# design.net
KiCad netlist of a schematic drawn in EasyEDA Pro
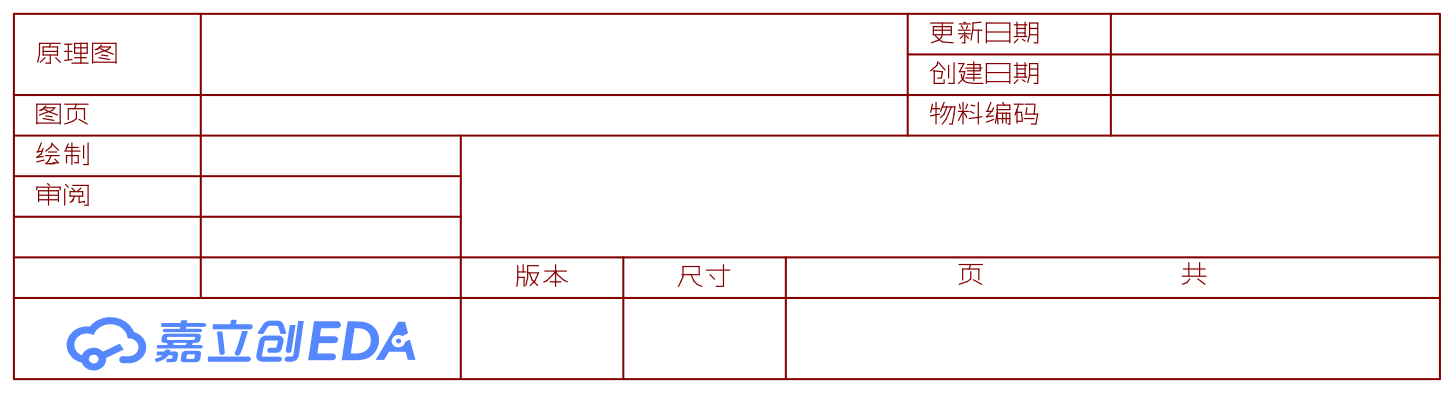
[diagram p0: 主控MCU]
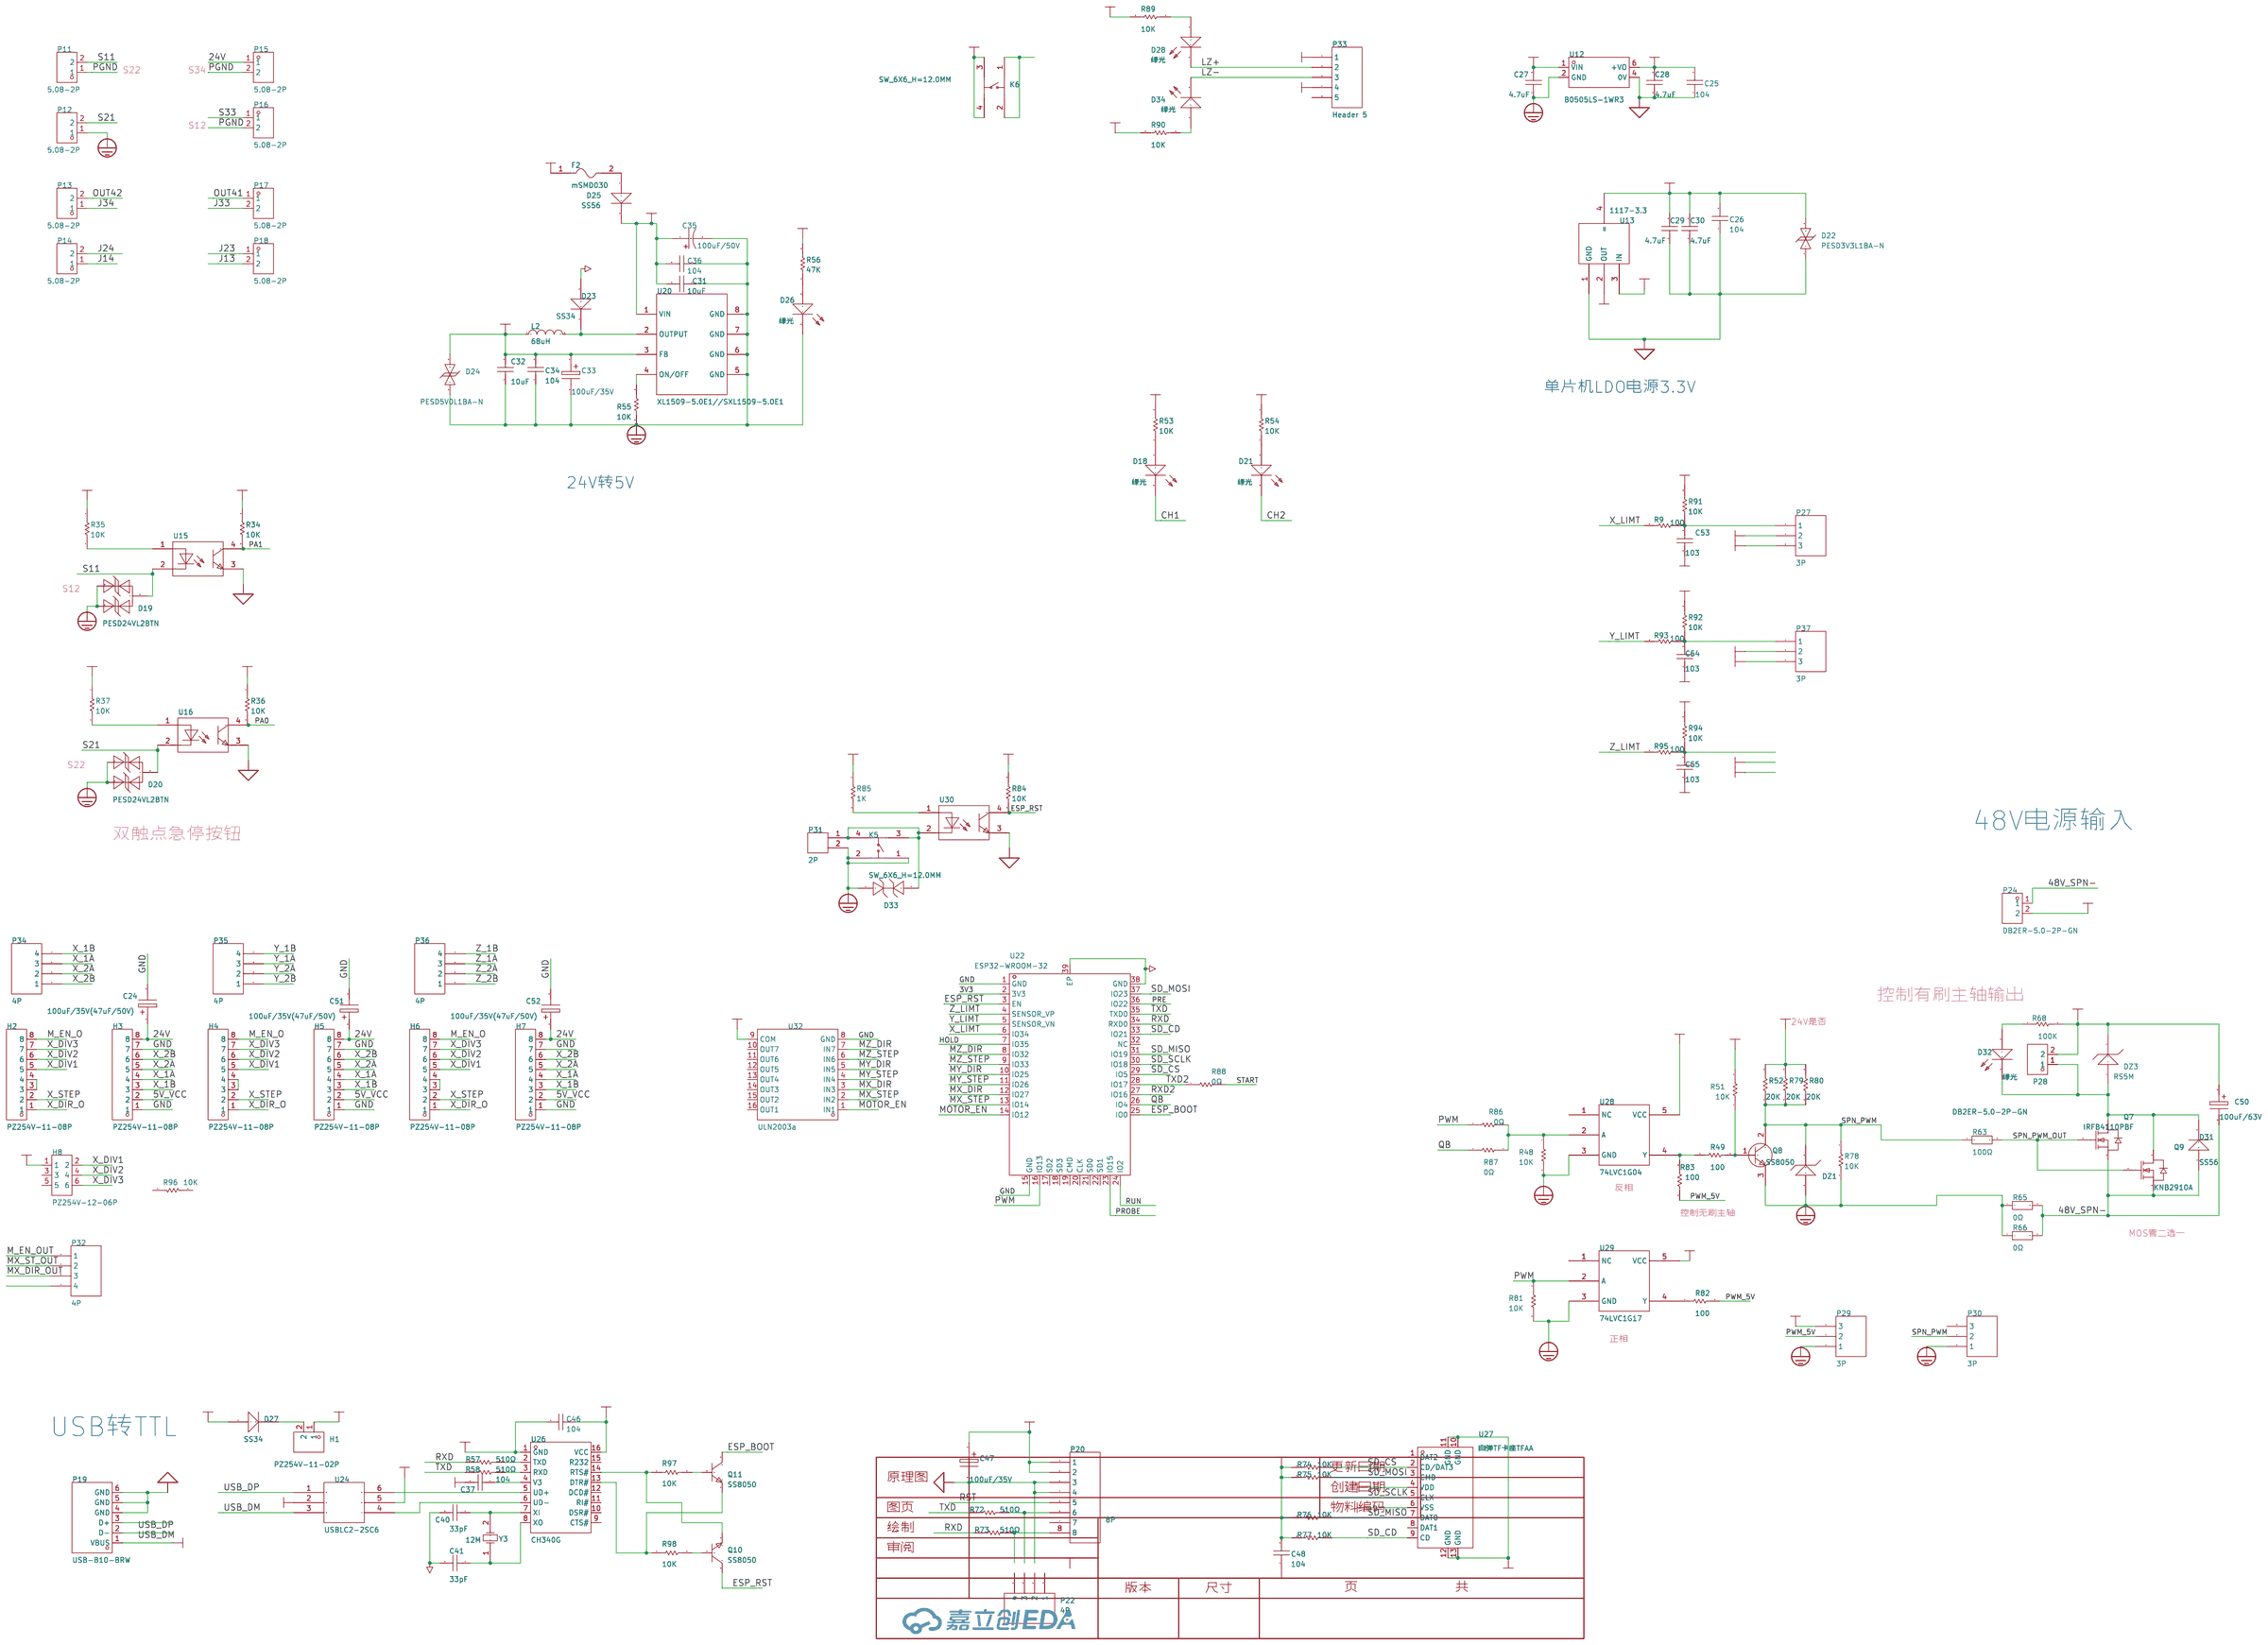
[diagram p1: 电源]

(export (version "E")
  (design (tool "Eeschema 10.0.6"))
  (components
    (comp (ref "C24")
      (value "100uF/35V(47uF/50V)")
      (footprint "easyedapro:电解电容贴片10x10")
      (libsource (lib "easyedapro") (part "ELECTRO1"))
    )
    (comp (ref "C25") (value "104") (libsource (lib "easyedapro") (part "CAP")))
    (comp (ref "C26")
      (value "104")
      (footprint "easyedapro:0603C")
      (description "Capacitor (Semiconductor SIM Model)")
      (libsource (lib "easyedapro") (part "Cap Semi"))
    )
    (comp (ref "C27") (value "4.7uF") (libsource (lib "easyedapro") (part "CAP")))
    (comp (ref "C28") (value "4.7uF") (libsource (lib "easyedapro") (part "CAP")))
    (comp (ref "C29") (value "4.7uF") (libsource (lib "easyedapro") (part "CAP")))
    (comp (ref "C30") (value "4.7uF") (libsource (lib "easyedapro") (part "CAP")))
    (comp (ref "C31") (value "10uF") (libsource (lib "easyedapro") (part "CAP")))
    (comp (ref "C32") (value "10uF") (libsource (lib "easyedapro") (part "CAP")))
    (comp (ref "C33")
      (value "100uF/35V")
      (footprint "easyedapro:0603C")
      (libsource (lib "easyedapro") (part "ELECTRO1"))
    )
    (comp (ref "C34")
      (value "104")
      (footprint "easyedapro:0603C")
      (description "Capacitor (Semiconductor SIM Model)")
      (libsource (lib "easyedapro") (part "Cap Semi"))
    )
    (comp (ref "C35")
      (value "100uF/50V")
      (footprint "easyedapro:CAP-SMD_BD10.0-L10.3-W10.3-LS11.0-R-RD")
      (fields (field (name "Manufacturer Part") "VZH101M1HTR-1008") (field (name "Manufacturer") "lelon(立隆)"))
      (libsource (lib "easyedapro") (part "VZH101M1HTR-1008"))
    )
    (comp (ref "C36")
      (value "104")
      (footprint "easyedapro:0603C")
      (description "Capacitor (Semiconductor SIM Model)")
      (libsource (lib "easyedapro") (part "Cap Semi"))
    )
    (comp (ref "C37")
      (value "104")
      (footprint "easyedapro:0603C")
      (description "Capacitor (Semiconductor SIM Model)")
      (libsource (lib "easyedapro") (part "Cap Semi"))
    )
    (comp (ref "C40")
      (value "18pF")
      (footprint "easyedapro:0603C")
      (description "Capacitor (Semiconductor SIM Model)")
      (libsource (lib "easyedapro") (part "Cap Semi"))
    )
    (comp (ref "C41")
      (value "18pF")
      (footprint "easyedapro:0603C")
      (description "Capacitor (Semiconductor SIM Model)")
      (libsource (lib "easyedapro") (part "Cap Semi"))
    )
    (comp (ref "C46")
      (value "104")
      (footprint "easyedapro:0603C")
      (description "Capacitor (Semiconductor SIM Model)")
      (libsource (lib "easyedapro") (part "Cap Semi"))
    )
    (comp (ref "C47")
      (value "100uF/35V")
      (footprint "easyedapro:电解电容贴片10x10")
      (libsource (lib "easyedapro") (part "ELECTRO1"))
    )
    (comp (ref "C48")
      (value "104")
      (footprint "easyedapro:11")
      (description "Capacitor (Semiconductor SIM Model)")
      (libsource (lib "easyedapro") (part "Cap Semi"))
    )
    (comp (ref "C50")
      (value "100uF/63V")
      (footprint "easyedapro:电解电容贴片10x10")
      (libsource (lib "easyedapro") (part "ELECTRO1"))
    )
    (comp (ref "C51")
      (value "100uF/35V(47uF/50V)")
      (footprint "easyedapro:电解电容贴片10x10")
      (libsource (lib "easyedapro") (part "ELECTRO1"))
    )
    (comp (ref "C52")
      (value "100uF/35V(47uF/50V)")
      (footprint "easyedapro:电解电容贴片10x10")
      (libsource (lib "easyedapro") (part "ELECTRO1"))
    )
    (comp (ref "C53") (value "103") (footprint "easyedapro:11") (libsource (lib "") (part "CAP_1")))
    (comp (ref "C54") (value "103") (footprint "easyedapro:11") (libsource (lib "") (part "CAP_1")))
    (comp (ref "C55") (value "103") (footprint "easyedapro:11") (libsource (lib "") (part "CAP_1")))
    (comp (ref "D18")
      (value "绿光")
      (footprint "easyedapro:0603LED")
      (libsource (lib "easyedapro") (part "LED"))
    )
    (comp (ref "D19")
      (value "PESD24VL2BTN")
      (footprint "easyedapro:SOT-23-3_L2.9-W1.6-P1.90-LS2.8-BR")
      (description "极性:Bidirectional;反向关断电压（典型值）:24V (Max);击穿电压（最小值）:26.7V;箝位电压:48V;峰值脉冲电流（10/1000us）:6A (8/20us);")
      (fields (field (name "Manufacturer") "BORN伯恩半导体"))
      (libsource (lib "easyedapro") (part "PESD24VL2BTN"))
    )
    (comp (ref "D20")
      (value "PESD24VL2BTN")
      (footprint "easyedapro:SOT-23-3_L2.9-W1.6-P1.90-LS2.8-BR")
      (description "极性:Bidirectional;反向关断电压（典型值）:24V (Max);击穿电压（最小值）:26.7V;箝位电压:48V;峰值脉冲电流（10/1000us）:6A (8/20us);")
      (fields (field (name "Manufacturer") "BORN伯恩半导体"))
      (libsource (lib "easyedapro") (part "PESD24VL2BTN"))
    )
    (comp (ref "D21")
      (value "绿光")
      (footprint "easyedapro:0603LED")
      (libsource (lib "easyedapro") (part "LED"))
    )
    (comp (ref "D22")
      (value "PESD3V3L1BA-N")
      (footprint "easyedapro:SOD-523_L1.2-W0.8-LS1.6-BI")
      (description "极性:Bidirectional;反向关断电压（典型值）:5V (Max);击穿电压（最小值）:6V;箝位电压:15V;峰值脉冲电流（10/1000us）:5A (8/20us);")
      (fields (field (name "Manufacturer") "BORN伯恩半导体"))
      (libsource (lib "easyedapro") (part "PESD5V0S1BBN"))
    )
    (comp (ref "D23") (value "SS34") (libsource (lib "easyedapro") (part "1N4148")))
    (comp (ref "D24")
      (value "PESD5V0L1BA-N")
      (footprint "easyedapro:SOD-523_L1.2-W0.8-LS1.6-BI")
      (description "极性:Bidirectional;反向关断电压（典型值）:5V (Max);击穿电压（最小值）:6V;箝位电压:15V;峰值脉冲电流（10/1000us）:5A (8/20us);")
      (fields (field (name "Manufacturer") "BORN伯恩半导体"))
      (libsource (lib "easyedapro") (part "PESD5V0S1BBN"))
    )
    (comp (ref "D25") (value "SS56") (footprint "easyedapro:SMA") (libsource (lib "") (part "1N4148_1")))
    (comp (ref "D26")
      (value "绿光")
      (footprint "easyedapro:0603LED")
      (libsource (lib "easyedapro") (part "LED"))
    )
    (comp (ref "D27") (value "SS34") (footprint "easyedapro:SMA") (libsource (lib "") (part "1N4148_1")))
    (comp (ref "D28")
      (value "绿光")
      (footprint "easyedapro:0603LED")
      (libsource (lib "easyedapro") (part "LED"))
    )
    (comp (ref "D31") (value "SS56") (libsource (lib "easyedapro") (part "1N4148")))
    (comp (ref "D32")
      (value "绿光")
      (footprint "easyedapro:0603LED")
      (libsource (lib "easyedapro") (part "LED"))
    )
    (comp (ref "D33")
      (value "ESD05V52D-C")
      (footprint "easyedapro:SOD-523_L1.2-W0.8-LS1.6-BI")
      (fields (field (name "Manufacturer") "TWGMC(台湾迪嘉)"))
      (libsource (lib "easyedapro") (part "ESD05V52D-C"))
    )
    (comp (ref "D34")
      (value "绿光")
      (footprint "easyedapro:0603LED")
      (libsource (lib "easyedapro") (part "LED"))
    )
    (comp (ref "DZ1") (value "--ѹ------SMAZ10V") (libsource (lib "easyedapro") (part "ѹ")))
    (comp (ref "DZ3") (value "RS5M") (libsource (lib "easyedapro") (part "ѹ")))
    (comp (ref "F2")
      (value "mSMD030")
      (footprint "easyedapro:F1812")
      (description "最大电压:30V;最大电流:100A;保持电流:300mA;跳闸电流:600mA;")
      (fields (field (name "Manufacturer") "台湾陆海"))
      (libsource (lib "easyedapro") (part "mSMD030"))
    )
    (comp (ref "H1")
      (value "PZ254V-11-02P")
      (footprint "easyedapro:HDR-TH_2P-P2.54-V-M")
      (fields (field (name "Manufacturer") "XFCN(兴飞)"))
      (libsource (lib "easyedapro") (part "PZ254V-11-02P"))
    )
    (comp (ref "H2")
      (value "PZ254V-11-08P")
      (footprint "easyedapro:HDR-TH_8P-P2.54-V-M")
      (fields (field (name "Manufacturer") "XFCN(兴飞)"))
      (libsource (lib "easyedapro") (part "PZ254V-11-08P"))
    )
    (comp (ref "H3")
      (value "PZ254V-11-08P")
      (footprint "easyedapro:HDR-TH_8P-P2.54-V-M")
      (fields (field (name "Manufacturer") "XFCN(兴飞)"))
      (libsource (lib "easyedapro") (part "PZ254V-11-08P"))
    )
    (comp (ref "H4")
      (value "PZ254V-11-08P")
      (footprint "easyedapro:HDR-TH_8P-P2.54-V-M")
      (fields (field (name "Manufacturer") "XFCN(兴飞)"))
      (libsource (lib "easyedapro") (part "PZ254V-11-08P"))
    )
    (comp (ref "H5")
      (value "PZ254V-11-08P")
      (footprint "easyedapro:HDR-TH_8P-P2.54-V-M")
      (fields (field (name "Manufacturer") "XFCN(兴飞)"))
      (libsource (lib "easyedapro") (part "PZ254V-11-08P"))
    )
    (comp (ref "H6")
      (value "PZ254V-11-08P")
      (footprint "easyedapro:HDR-TH_8P-P2.54-V-M")
      (fields (field (name "Manufacturer") "XFCN(兴飞)"))
      (libsource (lib "easyedapro") (part "PZ254V-11-08P"))
    )
    (comp (ref "H7")
      (value "PZ254V-11-08P")
      (footprint "easyedapro:HDR-TH_8P-P2.54-V-M")
      (fields (field (name "Manufacturer") "XFCN(兴飞)"))
      (libsource (lib "easyedapro") (part "PZ254V-11-08P"))
    )
    (comp (ref "H8")
      (value "PZ254V-12-06P")
      (footprint "easyedapro:HDR-TH_PZ254V-12-06P-A40")
      (description "排针2.54mm间距 直插 2x03位 直针外露4mm")
      (fields (field (name "Manufacturer") "XFCN(兴飞)"))
      (libsource (lib "easyedapro") (part "PZ254V-12-06P-A40"))
    )
    (comp (ref "K5")
      (value "SW_6X6_H=12.0MM")
      (footprint "easyedapro:KEY-SMD_4P-L6.0-W6.0-P4.50-LS9.0")
      (libsource (lib "easyedapro") (part "SW_6X6_H=12.0MM"))
    )
    (comp (ref "K6")
      (value "SW_6X6_H=12.0MM")
      (footprint "easyedapro:KEY-SMD_4P-L6.0-W6.0-P4.50-LS9.0")
      (libsource (lib "easyedapro") (part "SW_6X6_H=12.0MM"))
    )
    (comp (ref "L2")
      (value "68uH")
      (footprint "easyedapro:IND-SMD_L7.0-W7.0_SMDRI74-330MT")
      (description "电感值:33uH;精度:±20%;额定电流:960mA;饱和电流(Isat):1.8A;类型:屏蔽电感;")
      (fields (field (name "Manufacturer Part") "SMDRI74-330MT") (field (name "Manufacturer") "SXN(顺翔诺)"))
      (libsource (lib "easyedapro") (part "SMDRI74-330MT"))
    )
    (comp (ref "P11")
      (value "5.08-2P")
      (footprint "easyedapro:CONN-TH_2P-P5.08_DB128L-5.08-2P")
      (fields (field (name "Manufacturer") "DIBO(地博电气)"))
      (libsource (lib "easyedapro") (part "DB128L-5.08-2P"))
    )
    (comp (ref "P12")
      (value "5.08-2P")
      (footprint "easyedapro:CONN-TH_2P-P5.08_DB128L-5.08-2P")
      (fields (field (name "Manufacturer") "DIBO(地博电气)"))
      (libsource (lib "easyedapro") (part "DB128L-5.08-2P"))
    )
    (comp (ref "P13")
      (value "5.08-2P")
      (footprint "easyedapro:CONN-TH_2P-P5.08_DB128L-5.08-2P")
      (fields (field (name "Manufacturer") "DIBO(地博电气)"))
      (libsource (lib "easyedapro") (part "DB128L-5.08-2P"))
    )
    (comp (ref "P14")
      (value "5.08-2P")
      (footprint "easyedapro:CONN-TH_2P-P5.08_DB128L-5.08-2P")
      (fields (field (name "Manufacturer") "DIBO(地博电气)"))
      (libsource (lib "easyedapro") (part "DB128L-5.08-2P"))
    )
    (comp (ref "P15")
      (value "5.08-2P")
      (footprint "easyedapro:CONN-TH_2P-P5.08_DB128L-5.08-2P")
      (fields (field (name "Manufacturer") "DIBO(地博电气)"))
      (libsource (lib "easyedapro") (part "DB128L-5.08-2P"))
    )
    (comp (ref "P16")
      (value "5.08-2P")
      (footprint "easyedapro:CONN-TH_2P-P5.08_DB128L-5.08-2P")
      (fields (field (name "Manufacturer") "DIBO(地博电气)"))
      (libsource (lib "easyedapro") (part "DB128L-5.08-2P"))
    )
    (comp (ref "P17")
      (value "5.08-2P")
      (footprint "easyedapro:CONN-TH_2P-P5.08_DB128L-5.08-2P")
      (fields (field (name "Manufacturer") "DIBO(地博电气)"))
      (libsource (lib "easyedapro") (part "DB128L-5.08-2P"))
    )
    (comp (ref "P18")
      (value "5.08-2P")
      (footprint "easyedapro:CONN-TH_2P-P5.08_DB128L-5.08-2P")
      (fields (field (name "Manufacturer") "DIBO(地博电气)"))
      (libsource (lib "easyedapro") (part "DB128L-5.08-2P"))
    )
    (comp (ref "P19")
      (value "USB-B10-BRW")
      (footprint "easyedapro:USB-B-TH_USB-B10-BRW")
      (fields (field (name "Manufacturer") "XUNPU(讯普)"))
      (libsource (lib "easyedapro") (part "USB-B10-BRW"))
    )
    (comp (ref "P20") (value "8P") (footprint "easyedapro:IDC8") (libsource (lib "easyedapro") (part "8P")))
    (comp (ref "P22")
      (value "4P")
      (footprint "easyedapro:HDR1X4_CON")
      (libsource (lib "easyedapro") (part "4P"))
    )
    (comp (ref "P24")
      (value "DB2ER-5.0-2P-GN")
      (footprint "easyedapro:CONN-TH_2P-P5.00_DB2ER-5.0-2P-GN")
      (description "间距:5mm;颜色:绿色;排数:1;每排PIN数:2;额定电流:15A;额定电压:630V;触头镀层:锡;")
      (fields (field (name "Manufacturer") "DORABO(地博电气)"))
      (libsource (lib "easyedapro") (part "DB2ER-5.0-2P-GN"))
    )
    (comp (ref "P27")
      (value "3P")
      (footprint "easyedapro:HDR1X3_CON")
      (libsource (lib "easyedapro") (part "3P"))
    )
    (comp (ref "P28")
      (value "DB2ER-5.0-2P-GN")
      (footprint "easyedapro:CONN-TH_2P-P5.00_DB2ER-5.0-2P-GN")
      (description "间距:5mm;颜色:绿色;排数:1;每排PIN数:2;额定电流:15A;额定电压:630V;触头镀层:锡;")
      (fields (field (name "Manufacturer") "DORABO(地博电气)"))
      (libsource (lib "easyedapro") (part "DB2ER-5.0-2P-GN"))
    )
    (comp (ref "P29")
      (value "3P")
      (footprint "easyedapro:HDR1X3_CON")
      (libsource (lib "easyedapro") (part "3P"))
    )
    (comp (ref "P30")
      (value "3P")
      (footprint "easyedapro:HDR1X3_CON")
      (libsource (lib "easyedapro") (part "3P"))
    )
    (comp (ref "P31") (value "2P") (libsource (lib "easyedapro") (part "2P")))
    (comp (ref "P32")
      (value "4P")
      (footprint "easyedapro:HDR1X4_CON")
      (libsource (lib "easyedapro") (part "4P"))
    )
    (comp (ref "P33")
      (value "Header 5")
      (footprint "easyedapro:HDR1X5_CON")
      (description "Header, 5-Pin")
      (libsource (lib "easyedapro") (part "Header 5"))
    )
    (comp (ref "P34")
      (value "4P")
      (footprint "easyedapro:HDR1X4_CON")
      (libsource (lib "easyedapro") (part "4P"))
    )
    (comp (ref "P35")
      (value "4P")
      (footprint "easyedapro:HDR1X4_CON")
      (libsource (lib "easyedapro") (part "4P"))
    )
    (comp (ref "P36")
      (value "4P")
      (footprint "easyedapro:HDR1X4_CON")
      (libsource (lib "easyedapro") (part "4P"))
    )
    (comp (ref "P37")
      (value "3P")
      (footprint "easyedapro:HDR1X3_CON")
      (libsource (lib "easyedapro") (part "3P"))
    )
    (comp (ref "Q7")
      (value "IRFB4110PBF")
      (footprint "easyedapro:TO-220-3_L10.0-W4.5-P2.54-L")
      (fields (field (name "Manufacturer") "Infineon(英飞凌)"))
      (libsource (lib "easyedapro") (part "IRFB4110PBF"))
    )
    (comp (ref "Q8")
      (value "SS8050")
      (fields (field (name "Publisher") "Altium Limited"))
      (libsource (lib "easyedapro") (part "NPN"))
    )
    (comp (ref "Q9")
      (value "KNB2910A")
      (footprint "easyedapro:TO-263-2_L10.0-W9.1-P5.08-LS15.2-TL")
      (description "类型:-;漏源电压(Vdss):100V;连续漏极电流(Id):130A;导通电阻(RDS(on)):9mΩ@70V,10A;耗散功率(Pd):300W;阈值电压(Vgs(th)):4V;")
      (fields (field (name "Manufacturer") "KIA"))
      (libsource (lib "easyedapro") (part "KNB2910A"))
    )
    (comp (ref "Q10")
      (value "SS8050")
      (footprint "easyedapro:SOT-23-3_L2.9-W1.3-P1.90-LS2.4-BR")
      (fields (field (name "Manufacturer") "Doeshare(德芯)"))
      (libsource (lib "easyedapro") (part "SS8050_C2931717"))
    )
    (comp (ref "Q11")
      (value "SS8050")
      (footprint "easyedapro:SOT-23-3_L2.9-W1.3-P1.90-LS2.4-BR")
      (fields (field (name "Manufacturer") "Doeshare(德芯)"))
      (libsource (lib "easyedapro") (part "SS8050_C2931717"))
    )
    (comp (ref "R9")
      (value "100")
      (footprint "easyedapro:10")
      (description "Resistor")
      (libsource (lib "easyedapro") (part "RES"))
    )
    (comp (ref "R34")
      (value "10K")
      (footprint "easyedapro:0603R")
      (description "Resistor")
      (libsource (lib "easyedapro") (part "RES"))
    )
    (comp (ref "R35")
      (value "10K")
      (footprint "easyedapro:0603R")
      (description "Resistor")
      (libsource (lib "easyedapro") (part "RES"))
    )
    (comp (ref "R36")
      (value "10K")
      (footprint "easyedapro:0603R")
      (description "Resistor")
      (libsource (lib "easyedapro") (part "RES"))
    )
    (comp (ref "R37")
      (value "10K")
      (footprint "easyedapro:0603R")
      (description "Resistor")
      (libsource (lib "easyedapro") (part "RES"))
    )
    (comp (ref "R48")
      (value "10K")
      (description "Resistor")
      (fields (field (name "Publisher") "Altium Limited"))
      (libsource (lib "") (part "RES_1"))
    )
    (comp (ref "R49")
      (value "100")
      (description "Resistor")
      (fields (field (name "Publisher") "Altium Limited"))
      (libsource (lib "") (part "RES_1"))
    )
    (comp (ref "R51")
      (value "10K")
      (description "Resistor")
      (fields (field (name "Publisher") "Altium Limited"))
      (libsource (lib "") (part "RES_1"))
    )
    (comp (ref "R52")
      (value "20K")
      (description "Resistor")
      (fields (field (name "Publisher") "Altium Limited"))
      (libsource (lib "") (part "RES_1"))
    )
    (comp (ref "R53")
      (value "10K")
      (footprint "easyedapro:0603R")
      (description "Resistor")
      (libsource (lib "easyedapro") (part "RES"))
    )
    (comp (ref "R54")
      (value "10K")
      (footprint "easyedapro:0603R")
      (description "Resistor")
      (libsource (lib "easyedapro") (part "RES"))
    )
    (comp (ref "R55")
      (value "10K")
      (footprint "easyedapro:0603R")
      (description "Resistor")
      (libsource (lib "easyedapro") (part "RES"))
    )
    (comp (ref "R56")
      (value "47K")
      (footprint "easyedapro:0603R")
      (description "Resistor")
      (libsource (lib "easyedapro") (part "RES"))
    )
    (comp (ref "R57")
      (value "510Ω")
      (footprint "easyedapro:0603R")
      (description "Resistor")
      (libsource (lib "easyedapro") (part "RES"))
    )
    (comp (ref "R58")
      (value "510Ω")
      (footprint "easyedapro:0603R")
      (description "Resistor")
      (libsource (lib "easyedapro") (part "RES"))
    )
    (comp (ref "R63")
      (value "100Ω")
      (footprint "easyedapro:R1210")
      (libsource (lib "easyedapro") (part "电阻"))
    )
    (comp (ref "R65") (value "0Ω") (footprint "easyedapro:R1210") (libsource (lib "easyedapro") (part "电阻")))
    (comp (ref "R66") (value "0Ω") (footprint "easyedapro:R1210") (libsource (lib "easyedapro") (part "电阻")))
    (comp (ref "R68")
      (value "100K")
      (description "Resistor")
      (fields (field (name "Publisher") "Altium Limited"))
      (libsource (lib "") (part "RES_1"))
    )
    (comp (ref "R72")
      (value "510Ω")
      (footprint "easyedapro:0603R")
      (description "Resistor")
      (libsource (lib "easyedapro") (part "RES"))
    )
    (comp (ref "R73")
      (value "510Ω")
      (footprint "easyedapro:0603R")
      (description "Resistor")
      (libsource (lib "easyedapro") (part "RES"))
    )
    (comp (ref "R74")
      (value "10K")
      (footprint "easyedapro:10")
      (description "Resistor")
      (libsource (lib "easyedapro") (part "RES"))
    )
    (comp (ref "R75")
      (value "10K")
      (footprint "easyedapro:10")
      (description "Resistor")
      (libsource (lib "easyedapro") (part "RES"))
    )
    (comp (ref "R76")
      (value "10K")
      (footprint "easyedapro:10")
      (description "Resistor")
      (libsource (lib "easyedapro") (part "RES"))
    )
    (comp (ref "R77")
      (value "10K")
      (footprint "easyedapro:10")
      (description "Resistor")
      (libsource (lib "easyedapro") (part "RES"))
    )
    (comp (ref "R78")
      (value "10K")
      (description "Resistor")
      (fields (field (name "Publisher") "Altium Limited"))
      (libsource (lib "") (part "RES_1"))
    )
    (comp (ref "R79")
      (value "20K")
      (description "Resistor")
      (fields (field (name "Publisher") "Altium Limited"))
      (libsource (lib "") (part "RES_1"))
    )
    (comp (ref "R80")
      (value "20K")
      (description "Resistor")
      (fields (field (name "Publisher") "Altium Limited"))
      (libsource (lib "") (part "RES_1"))
    )
    (comp (ref "R81")
      (value "10K")
      (description "Resistor")
      (fields (field (name "Publisher") "Altium Limited"))
      (libsource (lib "") (part "RES_1"))
    )
    (comp (ref "R82")
      (value "100")
      (description "Resistor")
      (fields (field (name "Publisher") "Altium Limited"))
      (libsource (lib "") (part "RES_1"))
    )
    (comp (ref "R83")
      (value "100")
      (description "Resistor")
      (fields (field (name "Publisher") "Altium Limited"))
      (libsource (lib "") (part "RES_1"))
    )
    (comp (ref "R84")
      (value "10K")
      (footprint "easyedapro:0603R")
      (description "Resistor")
      (libsource (lib "easyedapro") (part "RES"))
    )
    (comp (ref "R85")
      (value "1K")
      (footprint "easyedapro:0603R")
      (description "Resistor")
      (libsource (lib "easyedapro") (part "RES"))
    )
    (comp (ref "R86")
      (value "0Ω")
      (description "Resistor")
      (fields (field (name "Publisher") "Altium Limited"))
      (libsource (lib "") (part "RES_1"))
    )
    (comp (ref "R87")
      (value "0Ω")
      (description "Resistor")
      (fields (field (name "Publisher") "Altium Limited"))
      (libsource (lib "") (part "RES_1"))
    )
    (comp (ref "R88")
      (value "0Ω")
      (description "Resistor")
      (fields (field (name "Publisher") "Altium Limited"))
      (libsource (lib "") (part "RES_1"))
    )
    (comp (ref "R89")
      (value "10K")
      (footprint "easyedapro:0603R")
      (description "Resistor")
      (libsource (lib "easyedapro") (part "RES"))
    )
    (comp (ref "R90")
      (value "10K")
      (footprint "easyedapro:0603R")
      (description "Resistor")
      (libsource (lib "easyedapro") (part "RES"))
    )
    (comp (ref "R91")
      (value "10K")
      (footprint "easyedapro:10")
      (description "Resistor")
      (libsource (lib "easyedapro") (part "RES"))
    )
    (comp (ref "R92")
      (value "10K")
      (footprint "easyedapro:10")
      (description "Resistor")
      (libsource (lib "easyedapro") (part "RES"))
    )
    (comp (ref "R93")
      (value "100")
      (footprint "easyedapro:10")
      (description "Resistor")
      (libsource (lib "easyedapro") (part "RES"))
    )
    (comp (ref "R94")
      (value "10K")
      (footprint "easyedapro:10")
      (description "Resistor")
      (libsource (lib "easyedapro") (part "RES"))
    )
    (comp (ref "R95")
      (value "100")
      (footprint "easyedapro:10")
      (description "Resistor")
      (libsource (lib "easyedapro") (part "RES"))
    )
    (comp (ref "R96")
      (value "10K")
      (footprint "easyedapro:0603R")
      (description "Resistor")
      (libsource (lib "easyedapro") (part "10K"))
    )
    (comp (ref "R97")
      (value "10K")
      (footprint "easyedapro:0603R")
      (description "Resistor")
      (libsource (lib "easyedapro") (part "RES"))
    )
    (comp (ref "R98")
      (value "10K")
      (footprint "easyedapro:0603R")
      (description "Resistor")
      (libsource (lib "easyedapro") (part "RES"))
    )
    (comp (ref "U12")
      (value "B0505LS-1WR3")
      (footprint "easyedapro:PWRM-TH_BXXXXLS-1WR3")
      (description "100%国产化器件，高可靠性，具备ROHS、REACH、CE认证产品")
      (fields (field (name "Manufacturer") "DEXU(德旭电子)"))
      (libsource (lib "easyedapro") (part "B0505LS-1WR3_C909800"))
    )
    (comp (ref "U13")
      (value "1117-3.3")
      (footprint "easyedapro:SOT-223")
      (libsource (lib "easyedapro") (part "LM1117"))
    )
    (comp (ref "U15")
      (value "LTV-357T-C")
      (footprint "easyedapro:SOP-4_L4.4-W3.9-P2.54-LS7.0-TL")
      (fields (field (name "Manufacturer") "LITEON(光宝)"))
      (libsource (lib "easyedapro") (part "LTV-357T-C"))
    )
    (comp (ref "U16")
      (value "LTV-357T-C")
      (footprint "easyedapro:SOP-4_L4.4-W3.9-P2.54-LS7.0-TL")
      (fields (field (name "Manufacturer") "LITEON(光宝)"))
      (libsource (lib "easyedapro") (part "LTV-357T-C"))
    )
    (comp (ref "U20")
      (value "XL1509-5.0E1//SXL1509-5.0E1")
      (footprint "easyedapro:SOIC-8_L5.0-W4.0-P1.27-LS6.0-BL")
      (description "功能类型:降压型;同步整流:-;输出通道数:-;拓扑结构:-;输入电压:-;输出电流(最大值):-;开关频率:-;")
      (fields (field (name "Manufacturer") "XLSEMI(芯龙)"))
      (libsource (lib "easyedapro") (part "XL1509-5.0E1"))
    )
    (comp (ref "U22")
      (value "ESP32-WROOM-32")
      (footprint "easyedapro:WIFIM-SMD_ESP-WROOM-32")
      (description "WiFi+双模蓝牙 双核CPU 网口 顶配MCU 低功耗蓝牙 ESP32系列ESP-WROOM-32模组/ESP-32S 4MB")
      (fields (field (name "Manufacturer") "ESPRESSIF(乐鑫)"))
      (libsource (lib "easyedapro") (part "ESP-WROOM-32"))
    )
    (comp (ref "U24")
      (value "USBLC2-2SC6")
      (footprint "easyedapro:SOT-23-6")
      (libsource (lib "easyedapro") (part "DIP6"))
    )
    (comp (ref "U26")
      (value "CH340G")
      (footprint "easyedapro:SOIC-16_L9.9-W3.9-P1.27-LS6.0-BL")
      (description "应用功能:收发器;接口协议:USB 2.0;数据速率:2Mbps;")
      (fields (field (name "Manufacturer") "WCH(南京沁恒)"))
      (libsource (lib "easyedapro") (part "CH340G"))
    )
    (comp (ref "U27")
      (value "自弹TF卡座TFAA")
      (footprint "easyedapro:SIM-SMD_C9900015645")
      (libsource (lib "easyedapro") (part "自弹TF卡座TFAA"))
    )
    (comp (ref "U28")
      (value "74LVC1G04")
      (footprint "easyedapro:SMD8")
      (libsource (lib "easyedapro") (part "74LVC1G04"))
    )
    (comp (ref "U29")
      (value "74LVC1G17")
      (footprint "easyedapro:SMD8")
      (libsource (lib "easyedapro") (part "74LVC1G04"))
    )
    (comp (ref "U30")
      (value "LTV-357T-C")
      (footprint "easyedapro:SOP-4_L4.4-W3.9-P2.54-LS7.0-TL")
      (fields (field (name "Manufacturer") "LITEON(光宝)"))
      (libsource (lib "easyedapro") (part "LTV-357T-C"))
    )
    (comp (ref "U32")
      (value "ULN2003a")
      (footprint "easyedapro:SOP-16_L9.9-W3.9-P1.27-LS6.0-BL")
      (description "通道数:七路;集射击穿电压(Vceo):50V;集电极电流(Ic):500mA;")
      (fields (field (name "Manufacturer") "GR(国睿)"))
      (libsource (lib "easyedapro") (part "ULN2003_C18164408"))
    )
    (comp (ref "Y3")
      (value "12M")
      (footprint "easyedapro:晶振贴片49SSMD")
      (description "Crystal Oscillator")
      (libsource (lib "easyedapro") (part "XTAL"))
    )
  )
  (nets
    (net (code "1") (name "3V3") (class "Default")
      (node (ref "C26") (pin "2") (pinfunction "2_2") (pintype "unspecified"))
      (node (ref "C29") (pin "2") (pinfunction "2_2") (pintype "input"))
      (node (ref "C30") (pin "2") (pinfunction "2_2") (pintype "input"))
      (node (ref "C48") (pin "2") (pinfunction "2_2") (pintype "unspecified"))
      (node (ref "D22") (pin "2") (pinfunction "2_2") (pintype "input"))
      (node (ref "R34") (pin "1") (pinfunction "1_1") (pintype "unspecified"))
      (node (ref "R36") (pin "1") (pinfunction "1_1") (pintype "unspecified"))
      (node (ref "R53") (pin "2") (pinfunction "2_2") (pintype "unspecified"))
      (node (ref "R54") (pin "2") (pinfunction "2_2") (pintype "unspecified"))
      (node (ref "R74") (pin "2") (pinfunction "2_2") (pintype "unspecified"))
      (node (ref "R75") (pin "2") (pinfunction "2_2") (pintype "unspecified"))
      (node (ref "R76") (pin "2") (pinfunction "2_2") (pintype "unspecified"))
      (node (ref "R77") (pin "2") (pinfunction "2_2") (pintype "unspecified"))
      (node (ref "R84") (pin "1") (pinfunction "1_1") (pintype "unspecified"))
      (node (ref "U13") (pin "2") (pinfunction "OUT_2") (pintype "unspecified"))
      (node (ref "U13") (pin "4") (pinfunction "=_4") (pintype "unspecified"))
      (node (ref "U22") (pin "2") (pinfunction "3V3_2") (pintype "unspecified"))
      (node (ref "U27") (pin "4") (pinfunction "VDD_4") (pintype "unspecified"))
    )
    (net (code "2") (name "5V_MCU") (class "Default")
      (node (ref "C25") (pin "2") (pinfunction "2_2") (pintype "input"))
      (node (ref "C28") (pin "2") (pinfunction "2_2") (pintype "input"))
      (node (ref "U12") (pin "6") (pinfunction "+VO_6") (pintype "unspecified"))
      (node (ref "U13") (pin "3") (pinfunction "IN_3") (pintype "unspecified"))
    )
    (net (code "3") (name "5V_VCC") (class "Default")
      (node (ref "C27") (pin "2") (pinfunction "2_2") (pintype "input"))
      (node (ref "C32") (pin "1") (pinfunction "1_1") (pintype "input"))
      (node (ref "C33") (pin "1") (pintype "unspecified"))
      (node (ref "C34") (pin "2") (pinfunction "2_2") (pintype "unspecified"))
      (node (ref "C46") (pin "1") (pinfunction "1_1") (pintype "unspecified"))
      (node (ref "C47") (pin "1") (pintype "unspecified"))
      (node (ref "D24") (pin "2") (pinfunction "2_2") (pintype "input"))
      (node (ref "H1") (pin "1") (pinfunction "1_1") (pintype "unspecified"))
      (node (ref "H3") (pin "2") (pinfunction "2_2") (pintype "unspecified"))
      (node (ref "H5") (pin "2") (pinfunction "2_2") (pintype "unspecified"))
      (node (ref "H7") (pin "2") (pinfunction "2_2") (pintype "unspecified"))
      (node (ref "H8") (pin "1") (pinfunction "1_1") (pintype "unspecified"))
      (node (ref "L2") (pin "1") (pinfunction "1_1") (pintype "unspecified"))
      (node (ref "P20") (pin "1") (pinfunction "1_1") (pintype "unspecified"))
      (node (ref "P20") (pin "2") (pinfunction "2_2") (pintype "unspecified"))
      (node (ref "P29") (pin "3") (pinfunction "3_3") (pintype "unspecified"))
      (node (ref "R51") (pin "2") (pinfunction "2_2") (pintype "input"))
      (node (ref "R85") (pin "1") (pinfunction "1_1") (pintype "unspecified"))
      (node (ref "U12") (pin "1") (pinfunction "VIN_1") (pintype "unspecified"))
      (node (ref "U20") (pin "3") (pinfunction "FB_3") (pintype "input"))
      (node (ref "U26") (pin "16") (pinfunction "VCC_16") (pintype "unspecified"))
      (node (ref "U28") (pin "5") (pinfunction "VCC_5") (pintype "unspecified"))
      (node (ref "U29") (pin "5") (pinfunction "VCC_5") (pintype "unspecified"))
      (node (ref "U32") (pin "9") (pinfunction "COM_9") (pintype "unspecified"))
    )
    (net (code "4") (name "12V") (class "Default")
      (node (ref "R52") (pin "2") (pinfunction "2_2") (pintype "input"))
      (node (ref "R79") (pin "2") (pinfunction "2_2") (pintype "input"))
      (node (ref "R80") (pin "2") (pinfunction "2_2") (pintype "input"))
    )
    (net (code "5") (name "24V") (class "Default")
      (node (ref "C24") (pin "1") (pintype "unspecified"))
      (node (ref "C51") (pin "1") (pintype "unspecified"))
      (node (ref "C52") (pin "1") (pintype "unspecified"))
      (node (ref "F2") (pin "1") (pinfunction "1_1") (pintype "input"))
      (node (ref "H3") (pin "8") (pinfunction "8_8") (pintype "unspecified"))
      (node (ref "H5") (pin "8") (pinfunction "8_8") (pintype "unspecified"))
      (node (ref "H7") (pin "8") (pinfunction "8_8") (pintype "unspecified"))
      (node (ref "P15") (pin "1") (pinfunction "1_1") (pintype "input"))
    )
    (net (code "6") (name "48V_SPN+") (class "Default")
      (node (ref "C50") (pin "1") (pintype "unspecified"))
      (node (ref "DZ3") (pin "2") (pinfunction "2_2") (pintype "input"))
      (node (ref "P24") (pin "2") (pinfunction "2_2") (pintype "unspecified"))
      (node (ref "P28") (pin "2") (pinfunction "2_2") (pintype "unspecified"))
      (node (ref "R68") (pin "2") (pinfunction "2_2") (pintype "input"))
    )
    (net (code "7") (name "48V_SPN-") (class "Default")
      (node (ref "C50") (pin "2") (pintype "unspecified"))
      (node (ref "D31") (pin "1") (pinfunction "1_1") (pintype "input"))
      (node (ref "P24") (pin "1") (pinfunction "1_1") (pintype "unspecified"))
      (node (ref "Q7") (pin "3") (pinfunction "S_3") (pintype "unspecified"))
      (node (ref "Q9") (pin "3") (pinfunction "S_3") (pintype "unspecified"))
      (node (ref "R65") (pin "2") (pinfunction "2_2") (pintype "input"))
      (node (ref "R66") (pin "2") (pinfunction "2_2") (pintype "input"))
    )
    (net (code "8") (name "CH1") (class "Default")
      (node (ref "D18") (pin "2") (pinfunction "2_2") (pintype "unspecified"))
    )
    (net (code "9") (name "CH2") (class "Default")
      (node (ref "D21") (pin "2") (pinfunction "2_2") (pintype "unspecified"))
    )
    (net (code "10") (name "ESP_BOOT") (class "Default")
      (node (ref "Q11") (pin "3") (pinfunction "C_3") (pintype "unspecified"))
      (node (ref "U22") (pin "25") (pinfunction "IO0_25") (pintype "unspecified"))
    )
    (net (code "11") (name "ESP_RST") (class "Default")
      (node (ref "Q10") (pin "3") (pinfunction "C_3") (pintype "unspecified"))
      (node (ref "R84") (pin "2") (pinfunction "2_2") (pintype "unspecified"))
      (node (ref "U22") (pin "3") (pinfunction "EN_3") (pintype "unspecified"))
      (node (ref "U30") (pin "4") (pinfunction "4_4") (pintype "unspecified"))
    )
    (net (code "12") (name "GND") (class "Default")
      (node (ref "C24") (pin "2") (pintype "unspecified"))
      (node (ref "C37") (pin "2") (pinfunction "2_2") (pintype "unspecified"))
      (node (ref "C40") (pin "2") (pinfunction "2_2") (pintype "unspecified"))
      (node (ref "C41") (pin "2") (pinfunction "2_2") (pintype "unspecified"))
      (node (ref "C46") (pin "2") (pinfunction "2_2") (pintype "unspecified"))
      (node (ref "C47") (pin "2") (pintype "unspecified"))
      (node (ref "C48") (pin "1") (pinfunction "1_1") (pintype "unspecified"))
      (node (ref "C51") (pin "2") (pintype "unspecified"))
      (node (ref "C52") (pin "2") (pintype "unspecified"))
      (node (ref "C53") (pin "1") (pinfunction "1_1") (pintype "unspecified"))
      (node (ref "C54") (pin "1") (pinfunction "1_1") (pintype "unspecified"))
      (node (ref "C55") (pin "1") (pinfunction "1_1") (pintype "unspecified"))
      (node (ref "D23") (pin "1") (pinfunction "1_1") (pintype "input"))
      (node (ref "D33") (pin "1") (pinfunction "1_1") (pintype "unspecified"))
      (node (ref "DZ1") (pin "1") (pinfunction "1_1") (pintype "input"))
      (node (ref "H3") (pin "1") (pinfunction "1_1") (pintype "unspecified"))
      (node (ref "H3") (pin "7") (pinfunction "7_7") (pintype "unspecified"))
      (node (ref "H5") (pin "1") (pinfunction "1_1") (pintype "unspecified"))
      (node (ref "H5") (pin "7") (pinfunction "7_7") (pintype "unspecified"))
      (node (ref "H7") (pin "1") (pinfunction "1_1") (pintype "unspecified"))
      (node (ref "H7") (pin "7") (pinfunction "7_7") (pintype "unspecified"))
      (node (ref "K5") (pin "1") (pinfunction "1_1") (pintype "unspecified"))
      (node (ref "K5") (pin "2") (pinfunction "2_2") (pintype "unspecified"))
      (node (ref "P19") (pin "4") (pinfunction "GND_4") (pintype "unspecified"))
      (node (ref "P19") (pin "5") (pinfunction "GND_5") (pintype "unspecified"))
      (node (ref "P19") (pin "6") (pinfunction "GND_6") (pintype "unspecified"))
      (node (ref "P20") (pin "3") (pinfunction "3_3") (pintype "unspecified"))
      (node (ref "P20") (pin "4") (pinfunction "4_4") (pintype "unspecified"))
      (node (ref "P27") (pin "2") (pinfunction "2_2") (pintype "unspecified"))
      (node (ref "P29") (pin "1") (pinfunction "1_1") (pintype "unspecified"))
      (node (ref "P30") (pin "1") (pinfunction "1_1") (pintype "unspecified"))
      (node (ref "P31") (pin "2") (pintype "input"))
      (node (ref "P33") (pin "1") (pinfunction "1_1") (pintype "unspecified"))
      (node (ref "P33") (pin "4") (pinfunction "4_4") (pintype "unspecified"))
      (node (ref "P37") (pin "2") (pinfunction "2_2") (pintype "unspecified"))
      (node (ref "Q8") (pin "3") (pinfunction "E_3") (pintype "input"))
      (node (ref "R48") (pin "2") (pinfunction "2_2") (pintype "input"))
      (node (ref "R65") (pin "1") (pinfunction "1_1") (pintype "input"))
      (node (ref "R66") (pin "1") (pinfunction "1_1") (pintype "input"))
      (node (ref "R78") (pin "2") (pinfunction "2_2") (pintype "input"))
      (node (ref "R81") (pin "2") (pinfunction "2_2") (pintype "input"))
      (node (ref "U22") (pin "1") (pinfunction "GND_1") (pintype "unspecified"))
      (node (ref "U22") (pin "15") (pinfunction "GND_15") (pintype "unspecified"))
      (node (ref "U22") (pin "38") (pinfunction "GND_38") (pintype "unspecified"))
      (node (ref "U22") (pin "39") (pinfunction "EP_39") (pintype "unspecified"))
      (node (ref "U24") (pin "2") (pinfunction "2_2") (pintype "unspecified"))
      (node (ref "U26") (pin "1") (pinfunction "GND_1") (pintype "unspecified"))
      (node (ref "U27") (pin "10") (pinfunction "GND_10") (pintype "unspecified"))
      (node (ref "U27") (pin "11") (pinfunction "GND_11") (pintype "unspecified"))
      (node (ref "U27") (pin "12") (pinfunction "GND_12") (pintype "unspecified"))
      (node (ref "U27") (pin "13") (pinfunction "GND_13") (pintype "unspecified"))
      (node (ref "U27") (pin "6") (pinfunction "VSS_6") (pintype "unspecified"))
      (node (ref "U28") (pin "3") (pinfunction "GND_3") (pintype "unspecified"))
      (node (ref "U29") (pin "3") (pinfunction "GND_3") (pintype "unspecified"))
      (node (ref "U30") (pin "3") (pinfunction "3_3") (pintype "unspecified"))
      (node (ref "U32") (pin "8") (pinfunction "GND_8") (pintype "unspecified"))
    )
    (net (code "13") (name "HOLD") (class "Default")
      (node (ref "U22") (pin "7") (pinfunction "IO35_7") (pintype "unspecified"))
    )
    (net (code "14") (name "J13") (class "Default")
      (node (ref "P18") (pin "2") (pinfunction "2_2") (pintype "input"))
    )
    (net (code "15") (name "J14") (class "Default")
      (node (ref "P14") (pin "1") (pinfunction "1_1") (pintype "input"))
    )
    (net (code "16") (name "J23") (class "Default")
      (node (ref "P18") (pin "1") (pinfunction "1_1") (pintype "input"))
    )
    (net (code "17") (name "J24") (class "Default")
      (node (ref "P14") (pin "2") (pinfunction "2_2") (pintype "input"))
    )
    (net (code "18") (name "J33") (class "Default")
      (node (ref "P17") (pin "2") (pinfunction "2_2") (pintype "input"))
    )
    (net (code "19") (name "J34") (class "Default")
      (node (ref "P13") (pin "1") (pinfunction "1_1") (pintype "input"))
    )
    (net (code "20") (name "LZ+") (class "Default")
      (node (ref "D28") (pin "2") (pinfunction "2_2") (pintype "unspecified"))
      (node (ref "P33") (pin "2") (pinfunction "2_2") (pintype "unspecified"))
    )
    (net (code "21") (name "LZ-") (class "Default")
      (node (ref "D34") (pin "2") (pinfunction "2_2") (pintype "unspecified"))
      (node (ref "P33") (pin "3") (pinfunction "3_3") (pintype "unspecified"))
    )
    (net (code "22") (name "MOTOR_EN") (class "Default")
      (node (ref "U22") (pin "14") (pinfunction "IO12_14") (pintype "unspecified"))
      (node (ref "U32") (pin "1") (pinfunction "IN1_1") (pintype "unspecified"))
    )
    (net (code "23") (name "MX_DIR") (class "Default")
      (node (ref "U22") (pin "12") (pinfunction "IO27_12") (pintype "unspecified"))
      (node (ref "U32") (pin "3") (pinfunction "IN3_3") (pintype "unspecified"))
    )
    (net (code "24") (name "MX_DIR_OUT") (class "Default")
      (node (ref "P32") (pin "3") (pinfunction "3_3") (pintype "unspecified"))
    )
    (net (code "25") (name "MX_STEP") (class "Default")
      (node (ref "U22") (pin "13") (pinfunction "IO14_13") (pintype "unspecified"))
      (node (ref "U32") (pin "2") (pinfunction "IN2_2") (pintype "unspecified"))
    )
    (net (code "26") (name "MX_ST_OUT") (class "Default")
      (node (ref "P32") (pin "2") (pinfunction "2_2") (pintype "unspecified"))
    )
    (net (code "27") (name "MY_DIR") (class "Default")
      (node (ref "U22") (pin "10") (pinfunction "IO25_10") (pintype "unspecified"))
      (node (ref "U32") (pin "5") (pinfunction "IN5_5") (pintype "unspecified"))
    )
    (net (code "28") (name "MY_STEP") (class "Default")
      (node (ref "U22") (pin "11") (pinfunction "IO26_11") (pintype "unspecified"))
      (node (ref "U32") (pin "4") (pinfunction "IN4_4") (pintype "unspecified"))
    )
    (net (code "29") (name "MZ_DIR") (class "Default")
      (node (ref "U22") (pin "8") (pinfunction "IO32_8") (pintype "unspecified"))
      (node (ref "U32") (pin "7") (pinfunction "IN7_7") (pintype "unspecified"))
    )
    (net (code "30") (name "MZ_STEP") (class "Default")
      (node (ref "U22") (pin "9") (pinfunction "IO33_9") (pintype "unspecified"))
      (node (ref "U32") (pin "6") (pinfunction "IN6_6") (pintype "unspecified"))
    )
    (net (code "31") (name "M_EN_O") (class "Default")
      (node (ref "H2") (pin "8") (pinfunction "8_8") (pintype "unspecified"))
      (node (ref "H4") (pin "8") (pinfunction "8_8") (pintype "unspecified"))
      (node (ref "H6") (pin "8") (pinfunction "8_8") (pintype "unspecified"))
    )
    (net (code "32") (name "M_EN_OUT") (class "Default")
      (node (ref "P32") (pin "1") (pinfunction "1_1") (pintype "unspecified"))
    )
    (net (code "33") (name "Net-(C53-Pad2)") (class "Default")
      (node (ref "C53") (pin "2") (pinfunction "2_2") (pintype "unspecified"))
      (node (ref "P27") (pin "1") (pinfunction "1_1") (pintype "unspecified"))
      (node (ref "R9") (pin "1") (pinfunction "1_1") (pintype "unspecified"))
      (node (ref "R91") (pin "1") (pinfunction "1_1") (pintype "unspecified"))
    )
    (net (code "34") (name "Net-(C54-Pad2)") (class "Default")
      (node (ref "C54") (pin "2") (pinfunction "2_2") (pintype "unspecified"))
      (node (ref "P37") (pin "1") (pinfunction "1_1") (pintype "unspecified"))
      (node (ref "R92") (pin "1") (pinfunction "1_1") (pintype "unspecified"))
      (node (ref "R93") (pin "1") (pinfunction "1_1") (pintype "unspecified"))
    )
    (net (code "35") (name "Net-(C55-Pad2)") (class "Default")
      (node (ref "C55") (pin "2") (pinfunction "2_2") (pintype "unspecified"))
      (node (ref "R94") (pin "1") (pinfunction "1_1") (pintype "unspecified"))
      (node (ref "R95") (pin "1") (pinfunction "1_1") (pintype "unspecified"))
    )
    (net (code "36") (name "Net-(D18-Pad1)") (class "Default")
      (node (ref "D18") (pin "1") (pinfunction "1_1") (pintype "unspecified"))
      (node (ref "R53") (pin "1") (pinfunction "1_1") (pintype "unspecified"))
    )
    (net (code "37") (name "Net-(D21-Pad1)") (class "Default")
      (node (ref "D21") (pin "1") (pinfunction "1_1") (pintype "unspecified"))
      (node (ref "R54") (pin "1") (pinfunction "1_1") (pintype "unspecified"))
    )
    (net (code "38") (name "Net-(D25-Pad1)") (class "Default")
      (node (ref "D25") (pin "1") (pinfunction "1_1") (pintype "unspecified"))
      (node (ref "F2") (pin "2") (pinfunction "2_2") (pintype "input"))
    )
    (net (code "39") (name "Net-(D26-Pad1)") (class "Default")
      (node (ref "D26") (pin "1") (pinfunction "1_1") (pintype "unspecified"))
      (node (ref "R56") (pin "1") (pinfunction "1_1") (pintype "unspecified"))
    )
    (net (code "40") (name "Net-(D27-Pad2)") (class "Default")
      (node (ref "D27") (pin "2") (pinfunction "2_2") (pintype "unspecified"))
      (node (ref "H1") (pin "2") (pinfunction "2_2") (pintype "unspecified"))
    )
    (net (code "41") (name "Net-(D28-Pad1)") (class "Default")
      (node (ref "D28") (pin "1") (pinfunction "1_1") (pintype "unspecified"))
      (node (ref "R89") (pin "1") (pinfunction "1_1") (pintype "unspecified"))
    )
    (net (code "42") (name "Net-(D32-Pad1)") (class "Default")
      (node (ref "D32") (pin "1") (pinfunction "1_1") (pintype "unspecified"))
      (node (ref "R68") (pin "1") (pinfunction "1_1") (pintype "input"))
    )
    (net (code "43") (name "Net-(D33-Pad2)") (class "Default")
      (node (ref "D33") (pin "2") (pinfunction "2_2") (pintype "unspecified"))
      (node (ref "K5") (pin "3") (pinfunction "3_3") (pintype "unspecified"))
      (node (ref "K5") (pin "4") (pinfunction "4_4") (pintype "unspecified"))
      (node (ref "P31") (pin "1") (pintype "input"))
      (node (ref "U30") (pin "2") (pinfunction "2_2") (pintype "unspecified"))
    )
    (net (code "44") (name "Net-(D34-Pad1)") (class "Default")
      (node (ref "D34") (pin "1") (pinfunction "1_1") (pintype "unspecified"))
      (node (ref "R90") (pin "1") (pinfunction "1_1") (pintype "unspecified"))
    )
    (net (code "45") (name "Net-(H2-Pad3)") (class "Default")
      (node (ref "H2") (pin "3") (pinfunction "3_3") (pintype "unspecified"))
      (node (ref "H2") (pin "4") (pinfunction "4_4") (pintype "unspecified"))
    )
    (net (code "46") (name "Net-(H4-Pad3)") (class "Default")
      (node (ref "H4") (pin "3") (pinfunction "3_3") (pintype "unspecified"))
      (node (ref "H4") (pin "4") (pinfunction "4_4") (pintype "unspecified"))
    )
    (net (code "47") (name "Net-(H6-Pad3)") (class "Default")
      (node (ref "H6") (pin "3") (pinfunction "3_3") (pintype "unspecified"))
      (node (ref "H6") (pin "4") (pinfunction "4_4") (pintype "unspecified"))
    )
    (net (code "48") (name "Net-(K6-Pad1)") (class "Default")
      (node (ref "K6") (pin "1") (pinfunction "1_1") (pintype "unspecified"))
      (node (ref "K6") (pin "2") (pinfunction "2_2") (pintype "unspecified"))
    )
    (net (code "49") (name "Net-(P20-Pad6)") (class "Default")
      (node (ref "P20") (pin "6") (pinfunction "6_6") (pintype "unspecified"))
      (node (ref "R72") (pin "2") (pinfunction "2_2") (pintype "unspecified"))
    )
    (net (code "50") (name "Net-(P20-Pad8)") (class "Default")
      (node (ref "P20") (pin "8") (pinfunction "8_8") (pintype "unspecified"))
      (node (ref "R73") (pin "2") (pinfunction "2_2") (pintype "unspecified"))
    )
    (net (code "51") (name "Net-(Q7-D)") (class "Default")
      (node (ref "D31") (pin "2") (pinfunction "2_2") (pintype "input"))
      (node (ref "D32") (pin "2") (pinfunction "2_2") (pintype "unspecified"))
      (node (ref "DZ3") (pin "1") (pinfunction "1_1") (pintype "input"))
      (node (ref "P28") (pin "1") (pinfunction "1_1") (pintype "unspecified"))
      (node (ref "Q7") (pin "2") (pinfunction "D_2") (pintype "unspecified"))
      (node (ref "Q9") (pin "4") (pinfunction "D_4") (pintype "unspecified"))
    )
    (net (code "52") (name "Net-(Q8-B)") (class "Default")
      (node (ref "Q8") (pin "1") (pinfunction "B_1") (pintype "input"))
      (node (ref "R49") (pin "2") (pinfunction "2_2") (pintype "input"))
      (node (ref "R51") (pin "1") (pinfunction "1_1") (pintype "input"))
    )
    (net (code "53") (name "Net-(Q10-B)") (class "Default")
      (node (ref "Q10") (pin "1") (pinfunction "B_1") (pintype "unspecified"))
      (node (ref "R98") (pin "2") (pinfunction "2_2") (pintype "unspecified"))
    )
    (net (code "54") (name "Net-(Q10-E)") (class "Default")
      (node (ref "Q10") (pin "2") (pinfunction "E_2") (pintype "unspecified"))
      (node (ref "R97") (pin "1") (pinfunction "1_1") (pintype "unspecified"))
      (node (ref "U26") (pin "14") (pinfunction "RTS#_14") (pintype "unspecified"))
    )
    (net (code "55") (name "Net-(Q11-B)") (class "Default")
      (node (ref "Q11") (pin "1") (pinfunction "B_1") (pintype "unspecified"))
      (node (ref "R97") (pin "2") (pinfunction "2_2") (pintype "unspecified"))
    )
    (net (code "56") (name "Net-(Q11-E)") (class "Default")
      (node (ref "Q11") (pin "2") (pinfunction "E_2") (pintype "unspecified"))
      (node (ref "R98") (pin "1") (pinfunction "1_1") (pintype "unspecified"))
      (node (ref "U26") (pin "13") (pinfunction "DTR#_13") (pintype "unspecified"))
    )
    (net (code "57") (name "Net-(R35-Pad2)") (class "Default")
      (node (ref "R35") (pin "2") (pinfunction "2_2") (pintype "unspecified"))
      (node (ref "U15") (pin "1") (pinfunction "1_1") (pintype "unspecified"))
    )
    (net (code "58") (name "Net-(R37-Pad2)") (class "Default")
      (node (ref "R37") (pin "2") (pinfunction "2_2") (pintype "unspecified"))
      (node (ref "U16") (pin "1") (pinfunction "1_1") (pintype "unspecified"))
    )
    (net (code "59") (name "Net-(R85-Pad2)") (class "Default")
      (node (ref "R85") (pin "2") (pinfunction "2_2") (pintype "unspecified"))
      (node (ref "U30") (pin "1") (pinfunction "1_1") (pintype "unspecified"))
    )
    (net (code "60") (name "Net-(U20-ON{slash}OFF)") (class "Default")
      (node (ref "R55") (pin "1") (pinfunction "1_1") (pintype "unspecified"))
      (node (ref "U20") (pin "4") (pinfunction "ON/OFF_4") (pintype "input"))
    )
    (net (code "61") (name "Net-(U20-OUTPUT)") (class "Default")
      (node (ref "D23") (pin "2") (pinfunction "2_2") (pintype "input"))
      (node (ref "L2") (pin "2") (pinfunction "2_2") (pintype "unspecified"))
      (node (ref "U20") (pin "2") (pinfunction "OUTPUT_2") (pintype "input"))
    )
    (net (code "62") (name "Net-(U26-RXD)") (class "Default")
      (node (ref "R58") (pin "1") (pinfunction "1_1") (pintype "unspecified"))
      (node (ref "U26") (pin "3") (pinfunction "RXD_3") (pintype "unspecified"))
    )
    (net (code "63") (name "Net-(U26-TXD)") (class "Default")
      (node (ref "R57") (pin "1") (pinfunction "1_1") (pintype "unspecified"))
      (node (ref "U26") (pin "2") (pinfunction "TXD_2") (pintype "unspecified"))
    )
    (net (code "64") (name "Net-(U26-UD+)") (class "Default")
      (node (ref "U24") (pin "6") (pinfunction "6_6") (pintype "unspecified"))
      (node (ref "U26") (pin "5") (pinfunction "UD+_5") (pintype "unspecified"))
    )
    (net (code "65") (name "Net-(U26-UD-)") (class "Default")
      (node (ref "U24") (pin "4") (pinfunction "4_4") (pintype "unspecified"))
      (node (ref "U26") (pin "6") (pinfunction "UD-_6") (pintype "unspecified"))
    )
    (net (code "66") (name "Net-(U26-V3)") (class "Default")
      (node (ref "C37") (pin "1") (pinfunction "1_1") (pintype "unspecified"))
      (node (ref "U26") (pin "4") (pinfunction "V3_4") (pintype "unspecified"))
    )
    (net (code "67") (name "Net-(U26-XI)") (class "Default")
      (node (ref "C40") (pin "1") (pinfunction "1_1") (pintype "unspecified"))
      (node (ref "U26") (pin "7") (pinfunction "XI_7") (pintype "unspecified"))
      (node (ref "Y3") (pin "2") (pinfunction "OSC2_2") (pintype "unspecified"))
    )
    (net (code "68") (name "Net-(U26-XO)") (class "Default")
      (node (ref "C41") (pin "1") (pinfunction "1_1") (pintype "unspecified"))
      (node (ref "U26") (pin "8") (pinfunction "XO_8") (pintype "unspecified"))
      (node (ref "Y3") (pin "1") (pinfunction "OSC1_1") (pintype "unspecified"))
    )
    (net (code "69") (name "Net-(U28-A)") (class "Default")
      (node (ref "R48") (pin "1") (pinfunction "1_1") (pintype "input"))
      (node (ref "R86") (pin "2") (pinfunction "2_2") (pintype "input"))
      (node (ref "R87") (pin "2") (pinfunction "2_2") (pintype "input"))
      (node (ref "U28") (pin "2") (pinfunction "A_2") (pintype "unspecified"))
    )
    (net (code "70") (name "Net-(U28-Y)") (class "Default")
      (node (ref "R49") (pin "1") (pinfunction "1_1") (pintype "input"))
      (node (ref "R83") (pin "2") (pinfunction "2_2") (pintype "input"))
      (node (ref "U28") (pin "4") (pinfunction "Y_4") (pintype "unspecified"))
    )
    (net (code "71") (name "Net-(U29-Y)") (class "Default")
      (node (ref "R82") (pin "1") (pinfunction "1_1") (pintype "input"))
      (node (ref "U29") (pin "4") (pinfunction "Y_4") (pintype "unspecified"))
    )
    (net (code "72") (name "OUT41") (class "Default")
      (node (ref "P17") (pin "1") (pinfunction "1_1") (pintype "input"))
    )
    (net (code "73") (name "OUT42") (class "Default")
      (node (ref "P13") (pin "2") (pinfunction "2_2") (pintype "input"))
    )
    (net (code "74") (name "PA0") (class "Default")
      (node (ref "R36") (pin "2") (pinfunction "2_2") (pintype "unspecified"))
      (node (ref "U16") (pin "4") (pinfunction "4_4") (pintype "unspecified"))
    )
    (net (code "75") (name "PA1") (class "Default")
      (node (ref "R34") (pin "2") (pinfunction "2_2") (pintype "unspecified"))
      (node (ref "U15") (pin "4") (pinfunction "4_4") (pintype "unspecified"))
    )
    (net (code "76") (name "PGND") (class "Default")
      (node (ref "C27") (pin "1") (pinfunction "1_1") (pintype "input"))
      (node (ref "C31") (pin "1") (pinfunction "1_1") (pintype "input"))
      (node (ref "C32") (pin "2") (pinfunction "2_2") (pintype "input"))
      (node (ref "C33") (pin "2") (pintype "unspecified"))
      (node (ref "C34") (pin "1") (pinfunction "1_1") (pintype "unspecified"))
      (node (ref "C35") (pin "2") (pinfunction "2_2") (pintype "input"))
      (node (ref "C36") (pin "1") (pinfunction "1_1") (pintype "unspecified"))
      (node (ref "D19") (pin "1") (pinfunction "K_1") (pintype "input"))
      (node (ref "D19") (pin "2") (pinfunction "K_2") (pintype "input"))
      (node (ref "D20") (pin "1") (pinfunction "K_1") (pintype "input"))
      (node (ref "D20") (pin "2") (pinfunction "K_2") (pintype "input"))
      (node (ref "D24") (pin "1") (pinfunction "1_1") (pintype "input"))
      (node (ref "D26") (pin "2") (pinfunction "2_2") (pintype "unspecified"))
      (node (ref "P11") (pin "1") (pinfunction "1_1") (pintype "input"))
      (node (ref "P12") (pin "1") (pinfunction "1_1") (pintype "input"))
      (node (ref "P15") (pin "2") (pinfunction "2_2") (pintype "input"))
      (node (ref "P16") (pin "2") (pinfunction "2_2") (pintype "input"))
      (node (ref "R55") (pin "2") (pinfunction "2_2") (pintype "unspecified"))
      (node (ref "U12") (pin "2") (pinfunction "GND_2") (pintype "unspecified"))
      (node (ref "U20") (pin "5") (pinfunction "GND_5") (pintype "input"))
      (node (ref "U20") (pin "6") (pinfunction "GND_6") (pintype "input"))
      (node (ref "U20") (pin "7") (pinfunction "GND_7") (pintype "input"))
      (node (ref "U20") (pin "8") (pinfunction "GND_8") (pintype "input"))
    )
    (net (code "77") (name "PRE") (class "Default")
      (node (ref "U22") (pin "36") (pinfunction "IO22_36") (pintype "unspecified"))
    )
    (net (code "78") (name "PROBE") (class "Default")
      (node (ref "U22") (pin "23") (pinfunction "IO15_23") (pintype "unspecified"))
    )
    (net (code "79") (name "PWM") (class "Default")
      (node (ref "R81") (pin "1") (pinfunction "1_1") (pintype "input"))
      (node (ref "R86") (pin "1") (pinfunction "1_1") (pintype "input"))
      (node (ref "U22") (pin "16") (pinfunction "IO13_16") (pintype "unspecified"))
      (node (ref "U29") (pin "2") (pinfunction "A_2") (pintype "unspecified"))
    )
    (net (code "80") (name "PWM_5V") (class "Default")
      (node (ref "P29") (pin "2") (pinfunction "2_2") (pintype "unspecified"))
      (node (ref "R82") (pin "2") (pinfunction "2_2") (pintype "input"))
      (node (ref "R83") (pin "1") (pinfunction "1_1") (pintype "input"))
    )
    (net (code "81") (name "QB") (class "Default")
      (node (ref "R87") (pin "1") (pinfunction "1_1") (pintype "input"))
      (node (ref "U22") (pin "26") (pinfunction "IO4_26") (pintype "unspecified"))
    )
    (net (code "82") (name "RST") (class "Default")
      (node (ref "P20") (pin "5") (pinfunction "5_5") (pintype "unspecified"))
    )
    (net (code "83") (name "RUN") (class "Default")
      (node (ref "U22") (pin "24") (pinfunction "IO2_24") (pintype "unspecified"))
    )
    (net (code "84") (name "RXD") (class "Default")
      (node (ref "R57") (pin "2") (pinfunction "2_2") (pintype "unspecified"))
      (node (ref "R73") (pin "1") (pinfunction "1_1") (pintype "unspecified"))
      (node (ref "U22") (pin "34") (pinfunction "RXD0_34") (pintype "unspecified"))
    )
    (net (code "85") (name "RXD2") (class "Default")
      (node (ref "U22") (pin "27") (pinfunction "IO16_27") (pintype "unspecified"))
    )
    (net (code "86") (name "S11") (class "Default")
      (node (ref "D19") (pin "3") (pinfunction "A_3") (pintype "input"))
      (node (ref "P11") (pin "2") (pinfunction "2_2") (pintype "input"))
      (node (ref "U15") (pin "2") (pinfunction "2_2") (pintype "unspecified"))
    )
    (net (code "87") (name "S21") (class "Default")
      (node (ref "D20") (pin "3") (pinfunction "A_3") (pintype "input"))
      (node (ref "P12") (pin "2") (pinfunction "2_2") (pintype "input"))
      (node (ref "U16") (pin "2") (pinfunction "2_2") (pintype "unspecified"))
    )
    (net (code "88") (name "S33") (class "Default")
      (node (ref "P16") (pin "1") (pinfunction "1_1") (pintype "input"))
    )
    (net (code "89") (name "SD_CD") (class "Default")
      (node (ref "R77") (pin "1") (pinfunction "1_1") (pintype "unspecified"))
      (node (ref "U22") (pin "33") (pinfunction "IO21_33") (pintype "unspecified"))
      (node (ref "U27") (pin "9") (pinfunction "CD_9") (pintype "unspecified"))
    )
    (net (code "90") (name "SD_CS") (class "Default")
      (node (ref "R74") (pin "1") (pinfunction "1_1") (pintype "unspecified"))
      (node (ref "U22") (pin "29") (pinfunction "IO5_29") (pintype "unspecified"))
      (node (ref "U27") (pin "2") (pinfunction "CD/DAT3_2") (pintype "unspecified"))
    )
    (net (code "91") (name "SD_MISO") (class "Default")
      (node (ref "R76") (pin "1") (pinfunction "1_1") (pintype "unspecified"))
      (node (ref "U22") (pin "31") (pinfunction "IO19_31") (pintype "unspecified"))
      (node (ref "U27") (pin "7") (pinfunction "DAT0_7") (pintype "unspecified"))
    )
    (net (code "92") (name "SD_MOSI") (class "Default")
      (node (ref "R75") (pin "1") (pinfunction "1_1") (pintype "unspecified"))
      (node (ref "U22") (pin "37") (pinfunction "IO23_37") (pintype "unspecified"))
      (node (ref "U27") (pin "3") (pinfunction "CMD_3") (pintype "unspecified"))
    )
    (net (code "93") (name "SD_SCLK") (class "Default")
      (node (ref "U22") (pin "30") (pinfunction "IO18_30") (pintype "unspecified"))
      (node (ref "U27") (pin "5") (pinfunction "CLX_5") (pintype "unspecified"))
    )
    (net (code "94") (name "SGND") (class "Default")
      (node (ref "C25") (pin "1") (pinfunction "1_1") (pintype "input"))
      (node (ref "C26") (pin "1") (pinfunction "1_1") (pintype "unspecified"))
      (node (ref "C28") (pin "1") (pinfunction "1_1") (pintype "input"))
      (node (ref "C29") (pin "1") (pinfunction "1_1") (pintype "input"))
      (node (ref "C30") (pin "1") (pinfunction "1_1") (pintype "input"))
      (node (ref "D22") (pin "1") (pinfunction "1_1") (pintype "input"))
      (node (ref "U12") (pin "4") (pinfunction "0V_4") (pintype "unspecified"))
      (node (ref "U13") (pin "1") (pinfunction "GND_1") (pintype "unspecified"))
      (node (ref "U15") (pin "3") (pinfunction "3_3") (pintype "unspecified"))
      (node (ref "U16") (pin "3") (pinfunction "3_3") (pintype "unspecified"))
    )
    (net (code "95") (name "SPN_PWM") (class "Default")
      (node (ref "DZ1") (pin "2") (pinfunction "2_2") (pintype "input"))
      (node (ref "P30") (pin "2") (pinfunction "2_2") (pintype "unspecified"))
      (node (ref "Q8") (pin "2") (pinfunction "C_2") (pintype "input"))
      (node (ref "R52") (pin "1") (pinfunction "1_1") (pintype "input"))
      (node (ref "R63") (pin "1") (pinfunction "1_1") (pintype "input"))
      (node (ref "R78") (pin "1") (pinfunction "1_1") (pintype "input"))
      (node (ref "R79") (pin "1") (pinfunction "1_1") (pintype "input"))
      (node (ref "R80") (pin "1") (pinfunction "1_1") (pintype "input"))
    )
    (net (code "96") (name "SPN_PWM_OUT") (class "Default")
      (node (ref "Q7") (pin "1") (pinfunction "G_1") (pintype "unspecified"))
      (node (ref "Q9") (pin "1") (pinfunction "G_1") (pintype "unspecified"))
      (node (ref "R63") (pin "2") (pinfunction "2_2") (pintype "input"))
    )
    (net (code "97") (name "START") (class "Default")
      (node (ref "R88") (pin "2") (pinfunction "2_2") (pintype "input"))
    )
    (net (code "98") (name "TXD") (class "Default")
      (node (ref "R58") (pin "2") (pinfunction "2_2") (pintype "unspecified"))
      (node (ref "R72") (pin "1") (pinfunction "1_1") (pintype "unspecified"))
      (node (ref "U22") (pin "35") (pinfunction "TXD0_35") (pintype "unspecified"))
    )
    (net (code "99") (name "TXD2") (class "Default")
      (node (ref "R88") (pin "1") (pinfunction "1_1") (pintype "input"))
      (node (ref "U22") (pin "28") (pinfunction "IO17_28") (pintype "unspecified"))
    )
    (net (code "100") (name "USB_DM") (class "Default")
      (node (ref "P19") (pin "2") (pinfunction "D-_2") (pintype "unspecified"))
      (node (ref "U24") (pin "3") (pinfunction "3_3") (pintype "unspecified"))
    )
    (net (code "101") (name "USB_DP") (class "Default")
      (node (ref "P19") (pin "3") (pinfunction "D+_3") (pintype "unspecified"))
      (node (ref "U24") (pin "1") (pinfunction "1_1") (pintype "unspecified"))
    )
    (net (code "102") (name "VCC") (class "Default")
      (node (ref "K6") (pin "3") (pinfunction "3_3") (pintype "unspecified"))
      (node (ref "K6") (pin "4") (pinfunction "4_4") (pintype "unspecified"))
      (node (ref "P27") (pin "3") (pinfunction "3_3") (pintype "unspecified"))
      (node (ref "P37") (pin "3") (pinfunction "3_3") (pintype "unspecified"))
      (node (ref "R89") (pin "2") (pinfunction "2_2") (pintype "unspecified"))
      (node (ref "R90") (pin "2") (pinfunction "2_2") (pintype "unspecified"))
      (node (ref "R91") (pin "2") (pinfunction "2_2") (pintype "unspecified"))
      (node (ref "R92") (pin "2") (pinfunction "2_2") (pintype "unspecified"))
      (node (ref "R94") (pin "2") (pinfunction "2_2") (pintype "unspecified"))
    )
    (net (code "103") (name "VIN_24V") (class "Default")
      (node (ref "C31") (pin "2") (pinfunction "2_2") (pintype "input"))
      (node (ref "C35") (pin "1") (pinfunction "1_1") (pintype "input"))
      (node (ref "C36") (pin "2") (pinfunction "2_2") (pintype "unspecified"))
      (node (ref "D25") (pin "2") (pinfunction "2_2") (pintype "unspecified"))
      (node (ref "R35") (pin "1") (pinfunction "1_1") (pintype "unspecified"))
      (node (ref "R37") (pin "1") (pinfunction "1_1") (pintype "unspecified"))
      (node (ref "R56") (pin "2") (pinfunction "2_2") (pintype "unspecified"))
      (node (ref "U20") (pin "1") (pinfunction "VIN_1") (pintype "input"))
    )
    (net (code "104") (name "VUSB") (class "Default")
      (node (ref "D27") (pin "1") (pinfunction "1_1") (pintype "unspecified"))
      (node (ref "P19") (pin "1") (pinfunction "VBUS_1") (pintype "unspecified"))
      (node (ref "U24") (pin "5") (pinfunction "5_5") (pintype "unspecified"))
    )
    (net (code "105") (name "X_1A") (class "Default")
      (node (ref "H3") (pin "4") (pinfunction "4_4") (pintype "unspecified"))
      (node (ref "H5") (pin "4") (pinfunction "4_4") (pintype "unspecified"))
      (node (ref "H7") (pin "4") (pinfunction "4_4") (pintype "unspecified"))
      (node (ref "P34") (pin "3") (pinfunction "3_3") (pintype "unspecified"))
    )
    (net (code "106") (name "X_1B") (class "Default")
      (node (ref "H3") (pin "3") (pinfunction "3_3") (pintype "unspecified"))
      (node (ref "H5") (pin "3") (pinfunction "3_3") (pintype "unspecified"))
      (node (ref "H7") (pin "3") (pinfunction "3_3") (pintype "unspecified"))
      (node (ref "P34") (pin "4") (pinfunction "4_4") (pintype "unspecified"))
    )
    (net (code "107") (name "X_2A") (class "Default")
      (node (ref "H3") (pin "5") (pinfunction "5_5") (pintype "unspecified"))
      (node (ref "H5") (pin "5") (pinfunction "5_5") (pintype "unspecified"))
      (node (ref "H7") (pin "5") (pinfunction "5_5") (pintype "unspecified"))
      (node (ref "P34") (pin "2") (pinfunction "2_2") (pintype "unspecified"))
    )
    (net (code "108") (name "X_2B") (class "Default")
      (node (ref "H3") (pin "6") (pinfunction "6_6") (pintype "unspecified"))
      (node (ref "H5") (pin "6") (pinfunction "6_6") (pintype "unspecified"))
      (node (ref "H7") (pin "6") (pinfunction "6_6") (pintype "unspecified"))
      (node (ref "P34") (pin "1") (pinfunction "1_1") (pintype "unspecified"))
    )
    (net (code "109") (name "X_DIR_O") (class "Default")
      (node (ref "H2") (pin "1") (pinfunction "1_1") (pintype "unspecified"))
      (node (ref "H4") (pin "1") (pinfunction "1_1") (pintype "unspecified"))
      (node (ref "H6") (pin "1") (pinfunction "1_1") (pintype "unspecified"))
    )
    (net (code "110") (name "X_DIV1") (class "Default")
      (node (ref "H2") (pin "5") (pinfunction "5_5") (pintype "unspecified"))
      (node (ref "H4") (pin "5") (pinfunction "5_5") (pintype "unspecified"))
      (node (ref "H6") (pin "5") (pinfunction "5_5") (pintype "unspecified"))
      (node (ref "H8") (pin "2") (pinfunction "2_2") (pintype "unspecified"))
    )
    (net (code "111") (name "X_DIV2") (class "Default")
      (node (ref "H2") (pin "6") (pinfunction "6_6") (pintype "unspecified"))
      (node (ref "H4") (pin "6") (pinfunction "6_6") (pintype "unspecified"))
      (node (ref "H6") (pin "6") (pinfunction "6_6") (pintype "unspecified"))
      (node (ref "H8") (pin "4") (pinfunction "4_4") (pintype "unspecified"))
    )
    (net (code "112") (name "X_DIV3") (class "Default")
      (node (ref "H2") (pin "7") (pinfunction "7_7") (pintype "unspecified"))
      (node (ref "H4") (pin "7") (pinfunction "7_7") (pintype "unspecified"))
      (node (ref "H6") (pin "7") (pinfunction "7_7") (pintype "unspecified"))
      (node (ref "H8") (pin "6") (pinfunction "6_6") (pintype "unspecified"))
    )
    (net (code "113") (name "X_LIMT") (class "Default")
      (node (ref "R9") (pin "2") (pinfunction "2_2") (pintype "unspecified"))
      (node (ref "U22") (pin "6") (pinfunction "IO34_6") (pintype "unspecified"))
    )
    (net (code "114") (name "X_STEP") (class "Default")
      (node (ref "H2") (pin "2") (pinfunction "2_2") (pintype "unspecified"))
      (node (ref "H4") (pin "2") (pinfunction "2_2") (pintype "unspecified"))
      (node (ref "H6") (pin "2") (pinfunction "2_2") (pintype "unspecified"))
    )
    (net (code "115") (name "Y_1A") (class "Default")
      (node (ref "P35") (pin "3") (pinfunction "3_3") (pintype "unspecified"))
    )
    (net (code "116") (name "Y_1B") (class "Default")
      (node (ref "P35") (pin "4") (pinfunction "4_4") (pintype "unspecified"))
    )
    (net (code "117") (name "Y_2A") (class "Default")
      (node (ref "P35") (pin "2") (pinfunction "2_2") (pintype "unspecified"))
    )
    (net (code "118") (name "Y_2B") (class "Default")
      (node (ref "P35") (pin "1") (pinfunction "1_1") (pintype "unspecified"))
    )
    (net (code "119") (name "Y_LIMT") (class "Default")
      (node (ref "R93") (pin "2") (pinfunction "2_2") (pintype "unspecified"))
      (node (ref "U22") (pin "5") (pinfunction "SENSOR_VN_5") (pintype "unspecified"))
    )
    (net (code "120") (name "Z_1A") (class "Default")
      (node (ref "P36") (pin "3") (pinfunction "3_3") (pintype "unspecified"))
    )
    (net (code "121") (name "Z_1B") (class "Default")
      (node (ref "P36") (pin "4") (pinfunction "4_4") (pintype "unspecified"))
    )
    (net (code "122") (name "Z_2A") (class "Default")
      (node (ref "P36") (pin "2") (pinfunction "2_2") (pintype "unspecified"))
    )
    (net (code "123") (name "Z_2B") (class "Default")
      (node (ref "P36") (pin "1") (pinfunction "1_1") (pintype "unspecified"))
    )
    (net (code "124") (name "Z_LIMT") (class "Default")
      (node (ref "R95") (pin "2") (pinfunction "2_2") (pintype "unspecified"))
      (node (ref "U22") (pin "4") (pinfunction "SENSOR_VP_4") (pintype "unspecified"))
    )
    (net (code "125") (name "unconnected-(H8-Pad3)") (class "Default")
      (node (ref "H8") (pin "3") (pinfunction "3_3") (pintype "unspecified"))
    )
    (net (code "126") (name "unconnected-(H8-Pad5)") (class "Default")
      (node (ref "H8") (pin "5") (pinfunction "5_5") (pintype "unspecified"))
    )
    (net (code "127") (name "unconnected-(P20-Pad7)") (class "Default")
      (node (ref "P20") (pin "7") (pinfunction "7_7") (pintype "unspecified"))
    )
    (net (code "128") (name "unconnected-(P22-Pad1)") (class "Default")
      (node (ref "P22") (pin "1") (pinfunction "1_1") (pintype "unspecified"))
    )
    (net (code "129") (name "unconnected-(P22-Pad2)") (class "Default")
      (node (ref "P22") (pin "2") (pinfunction "2_2") (pintype "unspecified"))
    )
    (net (code "130") (name "unconnected-(P22-Pad3)") (class "Default")
      (node (ref "P22") (pin "3") (pinfunction "3_3") (pintype "unspecified"))
    )
    (net (code "131") (name "unconnected-(P22-Pad4)") (class "Default")
      (node (ref "P22") (pin "4") (pinfunction "4_4") (pintype "unspecified"))
    )
    (net (code "132") (name "unconnected-(P30-Pad3)") (class "Default")
      (node (ref "P30") (pin "3") (pinfunction "3_3") (pintype "unspecified"))
    )
    (net (code "133") (name "unconnected-(P32-Pad4)") (class "Default")
      (node (ref "P32") (pin "4") (pinfunction "4_4") (pintype "unspecified"))
    )
    (net (code "134") (name "unconnected-(P33-Pad5)") (class "Default")
      (node (ref "P33") (pin "5") (pinfunction "5_5") (pintype "unspecified"))
    )
    (net (code "135") (name "unconnected-(R96-Pad1)") (class "Default")
      (node (ref "R96") (pin "1") (pinfunction "1_1") (pintype "unspecified"))
    )
    (net (code "136") (name "unconnected-(R96-Pad2)") (class "Default")
      (node (ref "R96") (pin "2") (pinfunction "2_2") (pintype "unspecified"))
    )
    (net (code "137") (name "unconnected-(U22-CLK-Pad20)") (class "Default")
      (node (ref "U22") (pin "20") (pinfunction "CLK_20") (pintype "unspecified"))
    )
    (net (code "138") (name "unconnected-(U22-CMD-Pad19)") (class "Default")
      (node (ref "U22") (pin "19") (pinfunction "CMD_19") (pintype "unspecified"))
    )
    (net (code "139") (name "unconnected-(U22-NC-Pad32)") (class "Default")
      (node (ref "U22") (pin "32") (pinfunction "NC_32") (pintype "unspecified"))
    )
    (net (code "140") (name "unconnected-(U22-SD0-Pad21)") (class "Default")
      (node (ref "U22") (pin "21") (pinfunction "SD0_21") (pintype "unspecified"))
    )
    (net (code "141") (name "unconnected-(U22-SD1-Pad22)") (class "Default")
      (node (ref "U22") (pin "22") (pinfunction "SD1_22") (pintype "unspecified"))
    )
    (net (code "142") (name "unconnected-(U22-SD2-Pad17)") (class "Default")
      (node (ref "U22") (pin "17") (pinfunction "SD2_17") (pintype "unspecified"))
    )
    (net (code "143") (name "unconnected-(U22-SD3-Pad18)") (class "Default")
      (node (ref "U22") (pin "18") (pinfunction "SD3_18") (pintype "unspecified"))
    )
    (net (code "144") (name "unconnected-(U26-CTS#-Pad9)") (class "Default")
      (node (ref "U26") (pin "9") (pinfunction "CTS#_9") (pintype "unspecified"))
    )
    (net (code "145") (name "unconnected-(U26-DCD#-Pad12)") (class "Default")
      (node (ref "U26") (pin "12") (pinfunction "DCD#_12") (pintype "unspecified"))
    )
    (net (code "146") (name "unconnected-(U26-DSR#-Pad10)") (class "Default")
      (node (ref "U26") (pin "10") (pinfunction "DSR#_10") (pintype "unspecified"))
    )
    (net (code "147") (name "unconnected-(U26-R232-Pad15)") (class "Default")
      (node (ref "U26") (pin "15") (pinfunction "R232_15") (pintype "unspecified"))
    )
    (net (code "148") (name "unconnected-(U26-RI#-Pad11)") (class "Default")
      (node (ref "U26") (pin "11") (pinfunction "RI#_11") (pintype "unspecified"))
    )
    (net (code "149") (name "unconnected-(U27-DAT1-Pad8)") (class "Default")
      (node (ref "U27") (pin "8") (pinfunction "DAT1_8") (pintype "unspecified"))
    )
    (net (code "150") (name "unconnected-(U27-DAT2-Pad1)") (class "Default")
      (node (ref "U27") (pin "1") (pinfunction "DAT2_1") (pintype "unspecified"))
    )
    (net (code "151") (name "unconnected-(U28-NC-Pad1)") (class "Default")
      (node (ref "U28") (pin "1") (pinfunction "NC_1") (pintype "unspecified"))
    )
    (net (code "152") (name "unconnected-(U29-NC-Pad1)") (class "Default")
      (node (ref "U29") (pin "1") (pinfunction "NC_1") (pintype "unspecified"))
    )
    (net (code "153") (name "unconnected-(U32-OUT1-Pad16)") (class "Default")
      (node (ref "U32") (pin "16") (pinfunction "OUT1_16") (pintype "unspecified"))
    )
    (net (code "154") (name "unconnected-(U32-OUT2-Pad15)") (class "Default")
      (node (ref "U32") (pin "15") (pinfunction "OUT2_15") (pintype "unspecified"))
    )
    (net (code "155") (name "unconnected-(U32-OUT3-Pad14)") (class "Default")
      (node (ref "U32") (pin "14") (pinfunction "OUT3_14") (pintype "unspecified"))
    )
    (net (code "156") (name "unconnected-(U32-OUT4-Pad13)") (class "Default")
      (node (ref "U32") (pin "13") (pinfunction "OUT4_13") (pintype "unspecified"))
    )
    (net (code "157") (name "unconnected-(U32-OUT5-Pad12)") (class "Default")
      (node (ref "U32") (pin "12") (pinfunction "OUT5_12") (pintype "unspecified"))
    )
    (net (code "158") (name "unconnected-(U32-OUT6-Pad11)") (class "Default")
      (node (ref "U32") (pin "11") (pinfunction "OUT6_11") (pintype "unspecified"))
    )
    (net (code "159") (name "unconnected-(U32-OUT7-Pad10)") (class "Default")
      (node (ref "U32") (pin "10") (pinfunction "OUT7_10") (pintype "unspecified"))
    )
  )
)
